# design.net
KiCad netlist of a schematic drawn in Altium Designer
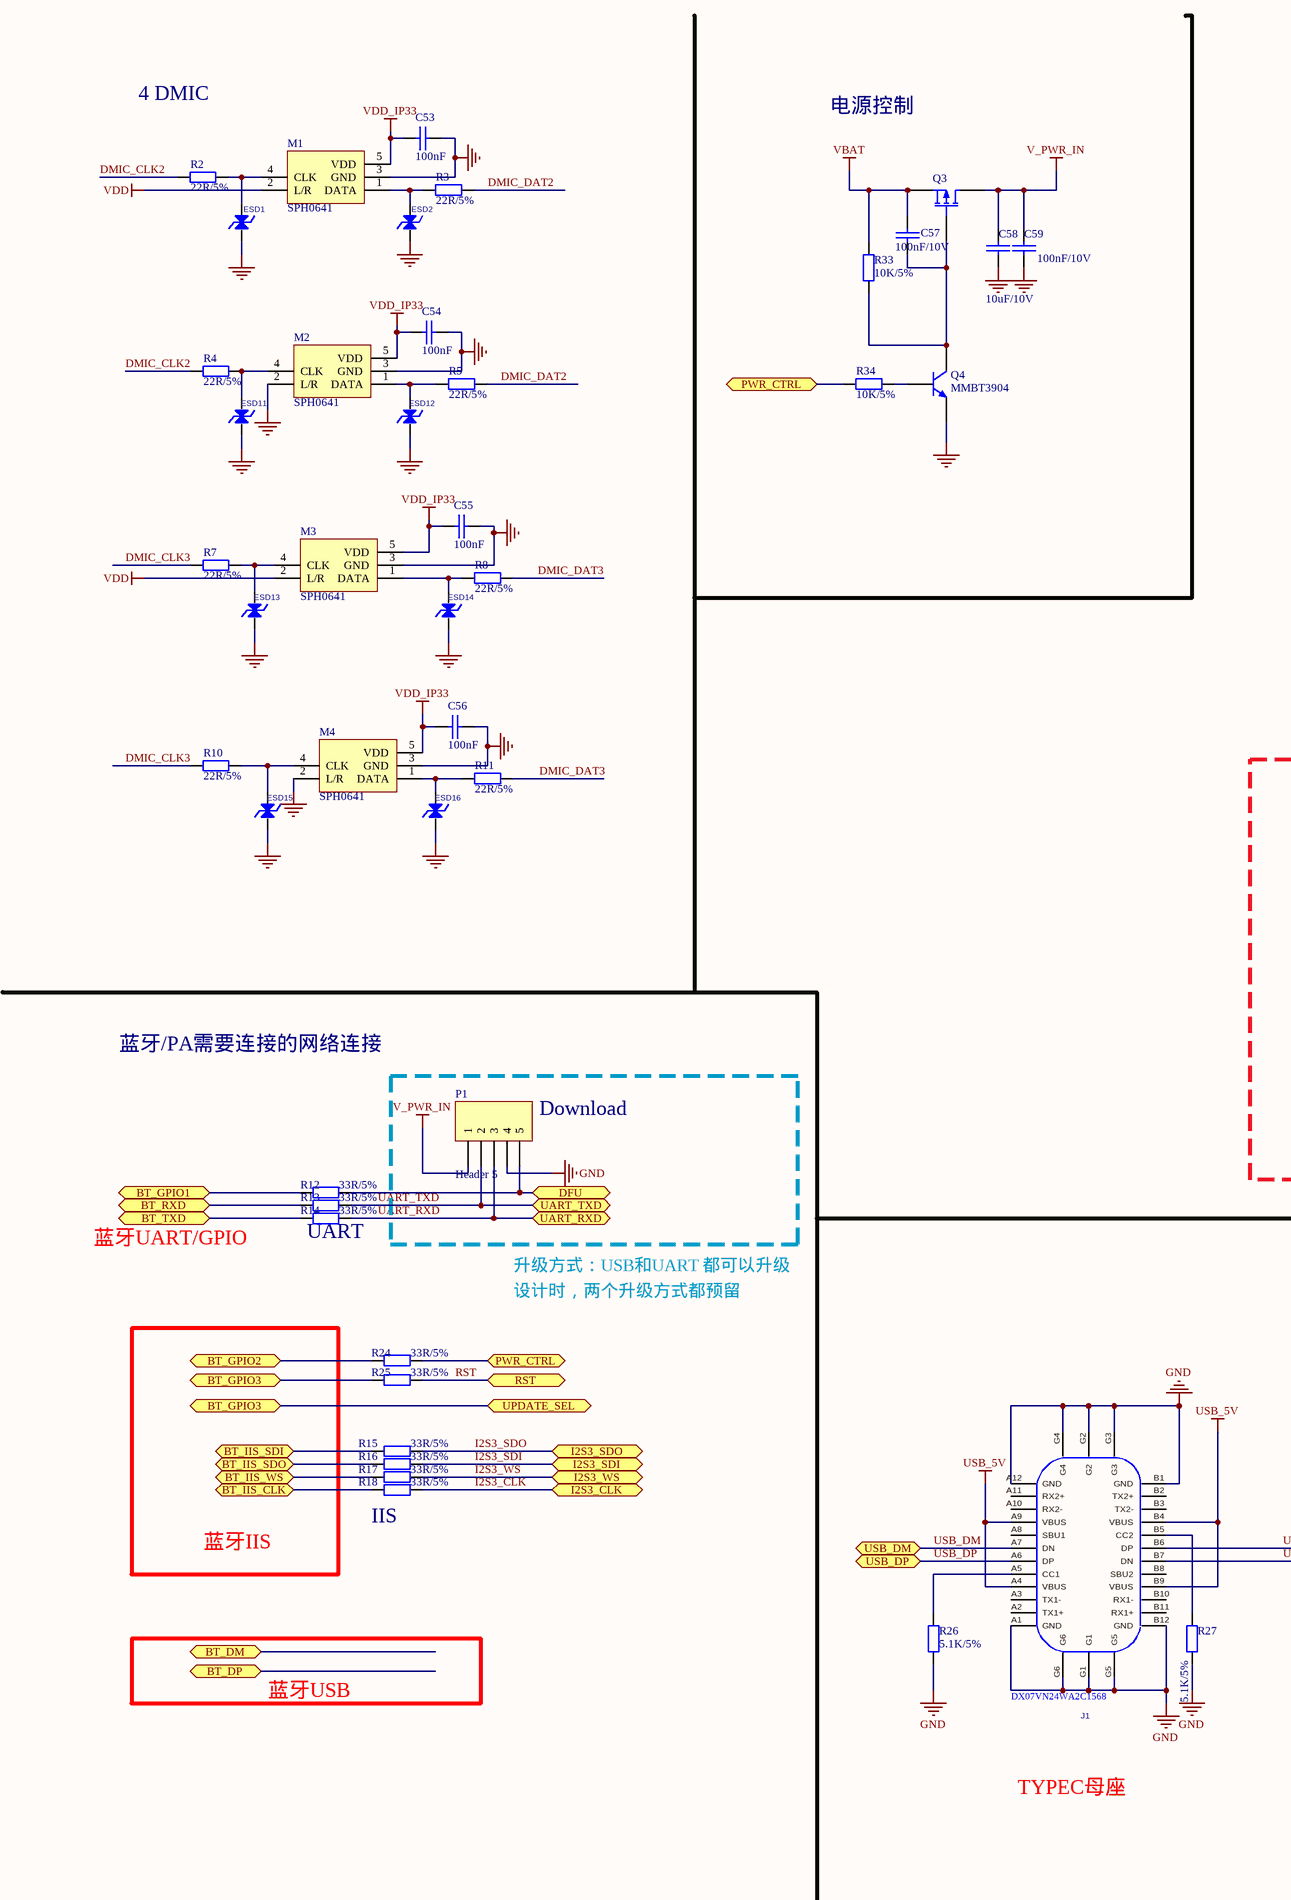
[diagram p0: 邮票孔参考设计.SchDoc, left]
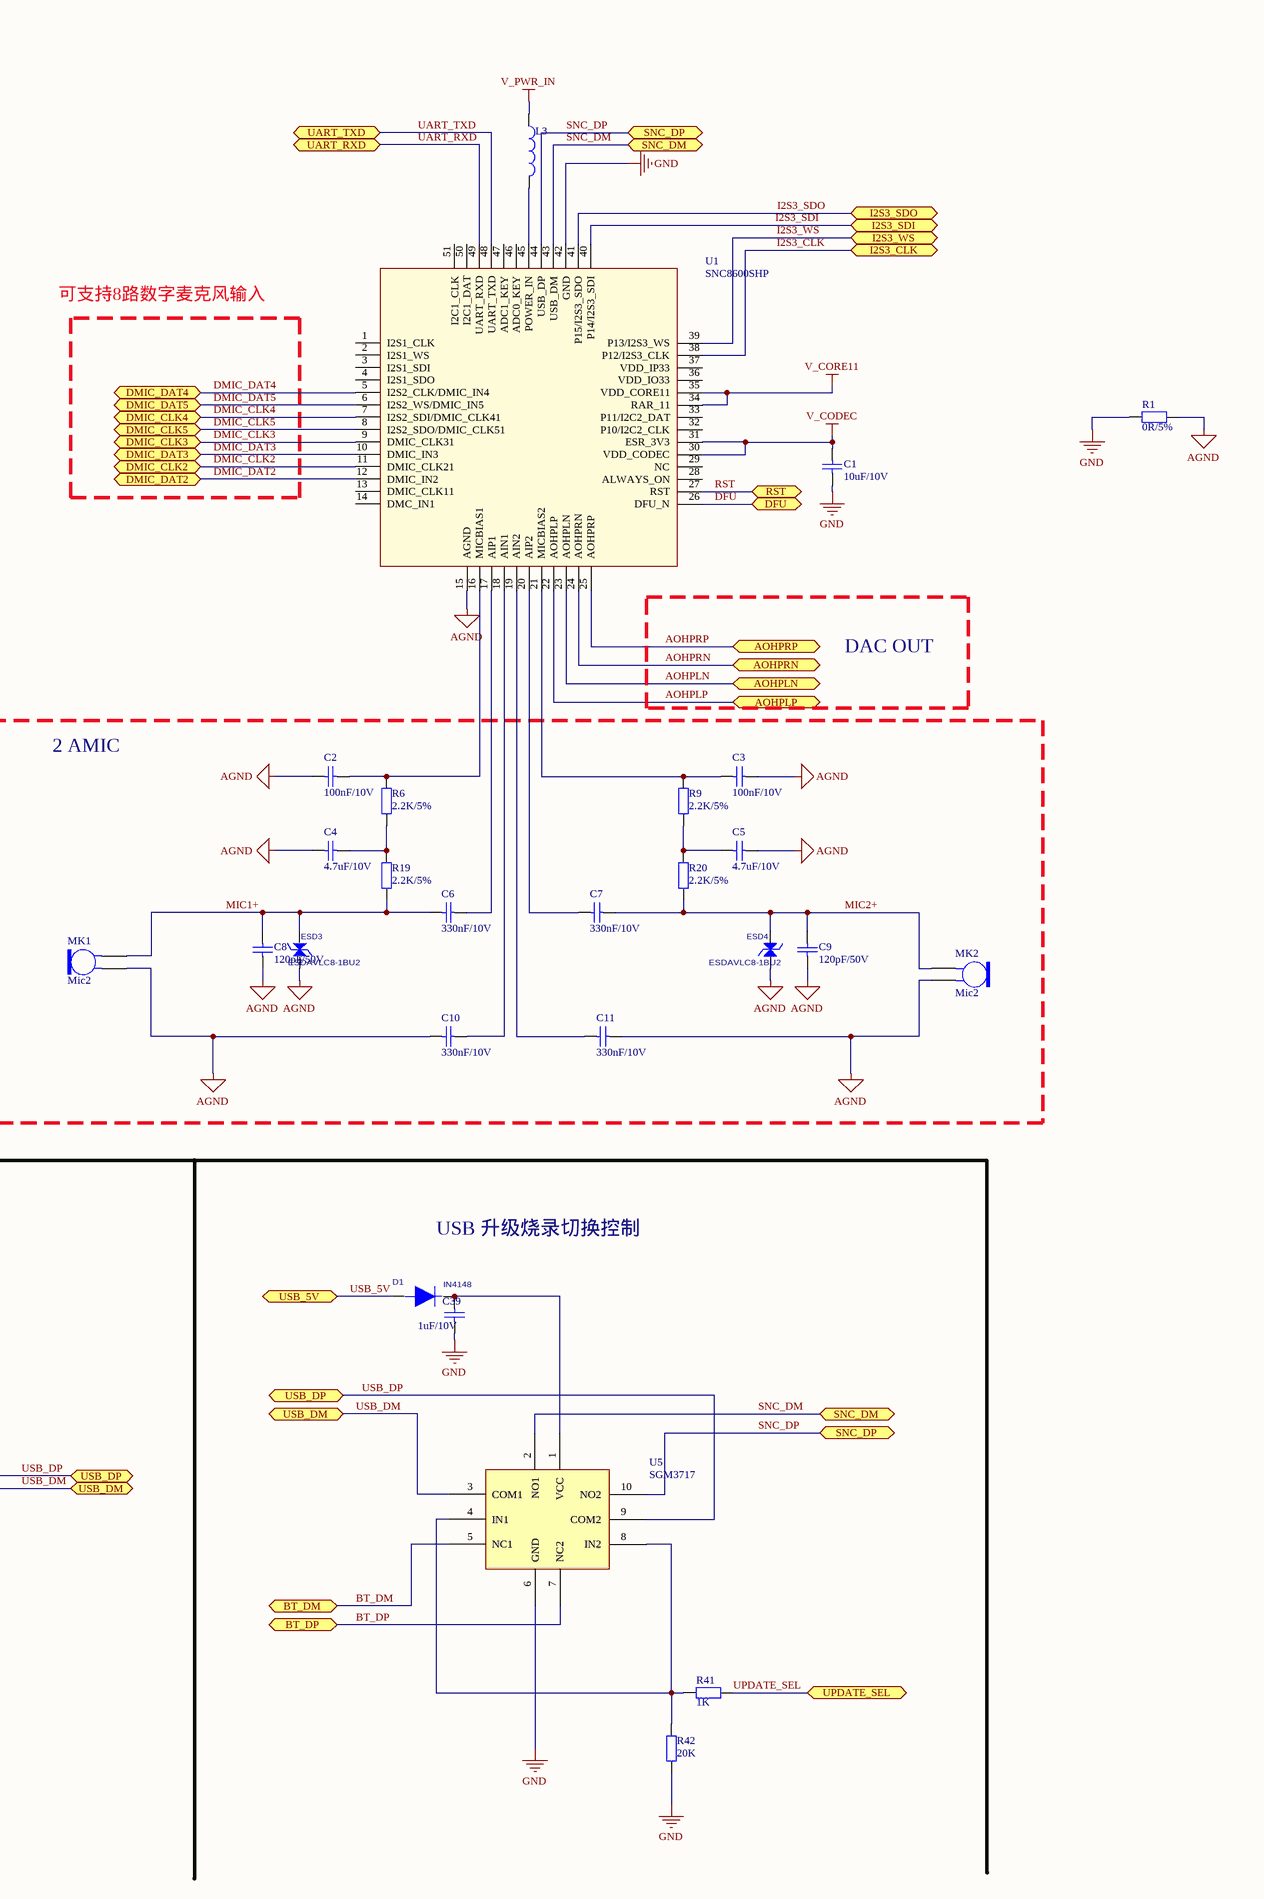
[diagram p1: 邮票孔参考设计.SchDoc, right]

(export (version "E")
  (design (tool "Eeschema 10.0.6"))
  (components
    (comp (ref "C1")
      (value "10uF/10V")
      (footprint "C0603")
      (description "Capacitor (Semiconductor SIM Model)")
      (fields (field (name "PUBLISHER") "Altium Limited"))
      (libsource (lib "Miscellaneous Devices") (part "Cap Semi"))
    )
    (comp (ref "C2")
      (value "100nF/10V")
      (footprint "C0402")
      (description "Capacitor (Semiconductor SIM Model)")
      (fields (field (name "PUBLISHER") "Altium Limited"))
      (libsource (lib "Miscellaneous Devices") (part "Cap Semi"))
    )
    (comp (ref "C3")
      (value "100nF/10V")
      (footprint "C0402")
      (description "Capacitor (Semiconductor SIM Model)")
      (fields (field (name "PUBLISHER") "Altium Limited"))
      (libsource (lib "Miscellaneous Devices") (part "Cap Semi"))
    )
    (comp (ref "C4")
      (value "4.7uF/10V")
      (footprint "0402")
      (description "Capacitor (Semiconductor SIM Model)")
      (fields (field (name "PUBLISHER") "Altium Limited"))
      (libsource (lib "Miscellaneous Devices") (part "Cap Semi"))
    )
    (comp (ref "C5")
      (value "4.7uF/10V")
      (footprint "0402")
      (description "Capacitor (Semiconductor SIM Model)")
      (fields (field (name "PUBLISHER") "Altium Limited"))
      (libsource (lib "Miscellaneous Devices") (part "Cap Semi"))
    )
    (comp (ref "C6")
      (value "330nF/10V")
      (footprint "C0402")
      (description "Capacitor (Semiconductor SIM Model)")
      (fields (field (name "PUBLISHER") "Altium Limited"))
      (libsource (lib "Miscellaneous Devices") (part "Cap Semi"))
    )
    (comp (ref "C7")
      (value "330nF/10V")
      (footprint "C0402")
      (description "Capacitor (Semiconductor SIM Model)")
      (fields (field (name "PUBLISHER") "Altium Limited"))
      (libsource (lib "Miscellaneous Devices") (part "Cap Semi"))
    )
    (comp (ref "C8")
      (value "120pF/50V")
      (footprint "C0402")
      (description "Capacitor (Semiconductor SIM Model)")
      (fields (field (name "PUBLISHER") "Altium Limited"))
      (libsource (lib "Miscellaneous Devices") (part "Cap Semi"))
    )
    (comp (ref "C9")
      (value "120pF/50V")
      (footprint "C0402")
      (description "Capacitor (Semiconductor SIM Model)")
      (fields (field (name "PUBLISHER") "Altium Limited"))
      (libsource (lib "Miscellaneous Devices") (part "Cap Semi"))
    )
    (comp (ref "C10")
      (value "330nF/10V")
      (footprint "C0402")
      (description "Capacitor (Semiconductor SIM Model)")
      (fields (field (name "PUBLISHER") "Altium Limited"))
      (libsource (lib "Miscellaneous Devices") (part "Cap Semi"))
    )
    (comp (ref "C11")
      (value "330nF/10V")
      (footprint "C0402")
      (description "Capacitor (Semiconductor SIM Model)")
      (fields (field (name "PUBLISHER") "Altium Limited"))
      (libsource (lib "Miscellaneous Devices") (part "Cap Semi"))
    )
    (comp (ref "C39")
      (value "1uF/10V")
      (footprint "C0603")
      (description "Capacitor (Semiconductor SIM Model)")
      (fields (field (name "PUBLISHER") "Altium Limited"))
      (libsource (lib "Miscellaneous Devices") (part "Cap Semi"))
    )
    (comp (ref "C53")
      (value "100nF")
      (footprint "0201")
      (description "Capacitor")
      (libsource (lib "MIC1") (part "CAP-0201"))
    )
    (comp (ref "C54")
      (value "100nF")
      (footprint "0201")
      (description "Capacitor")
      (libsource (lib "MIC1") (part "CAP-0201"))
    )
    (comp (ref "C55")
      (value "100nF")
      (footprint "0201")
      (description "Capacitor")
      (libsource (lib "MIC1") (part "CAP-0201"))
    )
    (comp (ref "C56")
      (value "100nF")
      (footprint "0201")
      (description "Capacitor")
      (libsource (lib "MIC1") (part "CAP-0201"))
    )
    (comp (ref "C57")
      (value "100nF/10V")
      (footprint "0201")
      (description "Capacitor")
      (libsource (lib "*") (part "CAP"))
    )
    (comp (ref "C58")
      (value "10uF/10V")
      (footprint "C0402")
      (description "Capacitor")
      (libsource (lib "电容") (part "普通电容"))
    )
    (comp (ref "C59")
      (value "100nF/10V")
      (footprint "0201")
      (description "Capacitor")
      (libsource (lib "电容") (part "普通电容"))
    )
    (comp (ref "D1")
      (value "IN4148")
      (footprint "SMD")
      (fields (field (name "Comment") "D-IN4148-SMT"))
      (libsource (lib "*") (part "D-IN4148-SMT"))
    )
    (comp (ref "ESD1")
      (value "~")
      (footprint "0402 DFN")
      (libsource (lib "EVB-SCH-LCD-202003152") (part "ESD"))
    )
    (comp (ref "ESD2")
      (value "~")
      (footprint "0402 DFN")
      (libsource (lib "EVB-SCH-LCD-202003152") (part "ESD"))
    )
    (comp (ref "ESD3")
      (value "ESDAVLC8-1BU2")
      (footprint "0402 DFN")
      (libsource (lib "EVB-SCH-LCD-202003152") (part "ESD"))
    )
    (comp (ref "ESD4")
      (value "ESDAVLC8-1BU2")
      (footprint "0402 DFN")
      (libsource (lib "EVB-SCH-LCD-202003152") (part "ESD"))
    )
    (comp (ref "ESD11")
      (value "~")
      (footprint "0402 DFN")
      (libsource (lib "EVB-SCH-LCD-202003152") (part "ESD"))
    )
    (comp (ref "ESD12")
      (value "~")
      (footprint "0402 DFN")
      (libsource (lib "EVB-SCH-LCD-202003152") (part "ESD"))
    )
    (comp (ref "ESD13")
      (value "~")
      (footprint "0402 DFN")
      (libsource (lib "EVB-SCH-LCD-202003152") (part "ESD"))
    )
    (comp (ref "ESD14")
      (value "~")
      (footprint "0402 DFN")
      (libsource (lib "EVB-SCH-LCD-202003152") (part "ESD"))
    )
    (comp (ref "ESD15")
      (value "~")
      (footprint "0402 DFN")
      (libsource (lib "EVB-SCH-LCD-202003152") (part "ESD"))
    )
    (comp (ref "ESD16")
      (value "~")
      (footprint "0402 DFN")
      (libsource (lib "EVB-SCH-LCD-202003152") (part "ESD"))
    )
    (comp (ref "J1")
      (value "TYPEC")
      (footprint "USB-TYPEC")
      (libsource (lib "EVB-SCH-LCD-202003152") (part "TYPEC"))
    )
    (comp (ref "L3")
      (value "~")
      (footprint "R0402")
      (description "Inductor")
      (fields (field (name "PUBLISHER") "Altium Limited"))
      (libsource (lib "Miscellaneous Devices") (part "Inductor"))
    )
    (comp (ref "M1")
      (value "SPH0641")
      (footprint "SPH_3526")
      (description "MEMS MICPHONE")
      (fields (field (name "PUBLISHER") "Altium Limited"))
      (libsource (lib "MIC1") (part "SPH0641"))
    )
    (comp (ref "M2")
      (value "SPH0641")
      (footprint "SPH_3526")
      (description "MEMS MICPHONE")
      (fields (field (name "PUBLISHER") "Altium Limited"))
      (libsource (lib "MIC1") (part "SPH0641"))
    )
    (comp (ref "M3")
      (value "SPH0641")
      (footprint "SPH_3526")
      (description "MEMS MICPHONE")
      (fields (field (name "PUBLISHER") "Altium Limited"))
      (libsource (lib "MIC1") (part "SPH0641"))
    )
    (comp (ref "M4")
      (value "SPH0641")
      (footprint "SPH_3526")
      (description "MEMS MICPHONE")
      (fields (field (name "PUBLISHER") "Altium Limited"))
      (libsource (lib "MIC1") (part "SPH0641"))
    )
    (comp (ref "MK1")
      (value "Mic2")
      (footprint "PIN2")
      (description "Microphone")
      (fields (field (name "PUBLISHER") "Altium Limited"))
      (libsource (lib "Miscellaneous Devices") (part "Mic2"))
    )
    (comp (ref "MK2")
      (value "Mic2")
      (footprint "PIN2")
      (description "Microphone")
      (fields (field (name "PUBLISHER") "Altium Limited"))
      (libsource (lib "Miscellaneous Devices") (part "Mic2"))
    )
    (comp (ref "P1")
      (value "Header 5")
      (footprint "HDR1X5")
      (description "Header, 5-Pin")
      (fields (field (name "PUBLISHER") "Altium Limited"))
      (libsource (lib "Miscellaneous Connectors") (part "Header 5"))
    )
    (comp (ref "Q3")
      (value "~")
      (footprint "SOT23_3407")
      (description "P-Channel MOSFET")
      (fields (field (name "PUBLISHER") "Altium Limited"))
      (libsource (lib "Miscellaneous Devices") (part "MOSFET-P"))
    )
    (comp (ref "Q4")
      (value "MMBT3904")
      (footprint "SOT23")
      (description "NPN General Purpose Amplifier")
      (fields (field (name "PUBLISHER") "Altium Limited"))
      (libsource (lib "Miscellaneous Devices") (part "2N3904"))
    )
    (comp (ref "R1")
      (value "0R/5%")
      (footprint "R0603")
      (description "Resistor")
      (fields (field (name "PUBLISHER") "Altium Limited"))
      (libsource (lib "") (part "Res2_2"))
    )
    (comp (ref "R2")
      (value "22R/5%")
      (footprint "0201")
      (description "Resistor")
      (fields (field (name "PUBLISHER") "Altium Limited"))
      (libsource (lib "Miscellaneous Devices") (part "Res2"))
    )
    (comp (ref "R3")
      (value "22R/5%")
      (footprint "0201")
      (description "Resistor")
      (fields (field (name "PUBLISHER") "Altium Limited"))
      (libsource (lib "Miscellaneous Devices") (part "Res2"))
    )
    (comp (ref "R4")
      (value "22R/5%")
      (footprint "0201")
      (description "Resistor")
      (fields (field (name "PUBLISHER") "Altium Limited"))
      (libsource (lib "Miscellaneous Devices") (part "Res2"))
    )
    (comp (ref "R5")
      (value "22R/5%")
      (footprint "0201")
      (description "Resistor")
      (fields (field (name "PUBLISHER") "Altium Limited"))
      (libsource (lib "Miscellaneous Devices") (part "Res2"))
    )
    (comp (ref "R6")
      (value "2.2K/5%")
      (footprint "R0402")
      (description "Resistor")
      (fields (field (name "PUBLISHER") "Altium Limited"))
      (libsource (lib "") (part "Res2_2"))
    )
    (comp (ref "R7")
      (value "22R/5%")
      (footprint "0201")
      (description "Resistor")
      (fields (field (name "PUBLISHER") "Altium Limited"))
      (libsource (lib "Miscellaneous Devices") (part "Res2"))
    )
    (comp (ref "R8")
      (value "22R/5%")
      (footprint "0201")
      (description "Resistor")
      (fields (field (name "PUBLISHER") "Altium Limited"))
      (libsource (lib "Miscellaneous Devices") (part "Res2"))
    )
    (comp (ref "R9")
      (value "2.2K/5%")
      (footprint "R0402")
      (description "Resistor")
      (fields (field (name "PUBLISHER") "Altium Limited"))
      (libsource (lib "") (part "Res2_1"))
    )
    (comp (ref "R10")
      (value "22R/5%")
      (footprint "0201")
      (description "Resistor")
      (fields (field (name "PUBLISHER") "Altium Limited"))
      (libsource (lib "Miscellaneous Devices") (part "Res2"))
    )
    (comp (ref "R11")
      (value "22R/5%")
      (footprint "0201")
      (description "Resistor")
      (fields (field (name "PUBLISHER") "Altium Limited"))
      (libsource (lib "Miscellaneous Devices") (part "Res2"))
    )
    (comp (ref "R12")
      (value "33R/5%")
      (footprint "R0603")
      (description "Resistor")
      (fields (field (name "PUBLISHER") "Altium Limited"))
      (libsource (lib "Miscellaneous Devices") (part "Res2"))
    )
    (comp (ref "R13")
      (value "33R/5%")
      (footprint "R0603")
      (description "Resistor")
      (fields (field (name "PUBLISHER") "Altium Limited"))
      (libsource (lib "Miscellaneous Devices") (part "Res2"))
    )
    (comp (ref "R14")
      (value "33R/5%")
      (footprint "R0603")
      (description "Resistor")
      (fields (field (name "PUBLISHER") "Altium Limited"))
      (libsource (lib "Miscellaneous Devices") (part "Res2"))
    )
    (comp (ref "R15")
      (value "33R/5%")
      (footprint "R0603")
      (description "Resistor")
      (fields (field (name "PUBLISHER") "Altium Limited"))
      (libsource (lib "Miscellaneous Devices") (part "Res2"))
    )
    (comp (ref "R16")
      (value "33R/5%")
      (footprint "R0603")
      (description "Resistor")
      (fields (field (name "PUBLISHER") "Altium Limited"))
      (libsource (lib "Miscellaneous Devices") (part "Res2"))
    )
    (comp (ref "R17")
      (value "33R/5%")
      (footprint "R0603")
      (description "Resistor")
      (fields (field (name "PUBLISHER") "Altium Limited"))
      (libsource (lib "Miscellaneous Devices") (part "Res2"))
    )
    (comp (ref "R18")
      (value "33R/5%")
      (footprint "R0603")
      (description "Resistor")
      (fields (field (name "PUBLISHER") "Altium Limited"))
      (libsource (lib "Miscellaneous Devices") (part "Res2"))
    )
    (comp (ref "R19")
      (value "2.2K/5%")
      (footprint "R0402")
      (description "Resistor")
      (fields (field (name "PUBLISHER") "Altium Limited"))
      (libsource (lib "") (part "Res2_2"))
    )
    (comp (ref "R20")
      (value "2.2K/5%")
      (footprint "R0402")
      (description "Resistor")
      (fields (field (name "PUBLISHER") "Altium Limited"))
      (libsource (lib "") (part "Res2_1"))
    )
    (comp (ref "R24")
      (value "33R/5%")
      (footprint "R0603")
      (description "Resistor")
      (fields (field (name "PUBLISHER") "Altium Limited"))
      (libsource (lib "Miscellaneous Devices") (part "Res2"))
    )
    (comp (ref "R25")
      (value "33R/5%")
      (footprint "R0603")
      (description "Resistor")
      (fields (field (name "PUBLISHER") "Altium Limited"))
      (libsource (lib "Miscellaneous Devices") (part "Res2"))
    )
    (comp (ref "R26")
      (value "5.1K/5%")
      (footprint "R0603")
      (description "Resistor")
      (fields (field (name "PUBLISHER") "Altium Limited"))
      (libsource (lib "") (part "Res2_1"))
    )
    (comp (ref "R27")
      (value "5.1K/5%")
      (footprint "R0603")
      (description "Resistor")
      (fields (field (name "PUBLISHER") "Altium Limited"))
      (libsource (lib "") (part "Res2_1"))
    )
    (comp (ref "R33")
      (value "10K/5%")
      (footprint "0201")
      (description "Resistor")
      (fields (field (name "PUBLISHER") "Altium Limited"))
      (libsource (lib "") (part "Res2_1"))
    )
    (comp (ref "R34")
      (value "10K/5%")
      (footprint "0201")
      (description "Resistor")
      (fields (field (name "PUBLISHER") "Altium Limited"))
      (libsource (lib "Miscellaneous Devices") (part "Res2"))
    )
    (comp (ref "R41")
      (value "1K")
      (footprint "R0603")
      (description "Resistor")
      (fields (field (name "PUBLISHER") "Altium Limited"))
      (libsource (lib "") (part "Res2_2"))
    )
    (comp (ref "R42")
      (value "20K")
      (footprint "R0603")
      (description "Resistor")
      (fields (field (name "PUBLISHER") "Altium Limited"))
      (libsource (lib "") (part "Res2_1"))
    )
    (comp (ref "U1") (value "SNC8600SHP") (libsource (lib "EVB-SCH-LCD-202003152") (part "SNC8600SHP")))
    (comp (ref "U5")
      (value "SGM3717")
      (footprint "UQFN10")
      (libsource (lib "EVB-SCH-LCD-202003152") (part "NLAS2750"))
    )
  )
  (nets
    (net (code "1") (name "/AOHPLN") (class "Default")
      (node (ref "U1") (pin "23") (pinfunction "AOHPLN_23") (pintype "passive"))
    )
    (net (code "2") (name "/AOHPLP") (class "Default")
      (node (ref "U1") (pin "22") (pinfunction "AOHPLP_22") (pintype "passive"))
    )
    (net (code "3") (name "/AOHPRN") (class "Default")
      (node (ref "U1") (pin "24") (pinfunction "AOHPRN_24") (pintype "passive"))
    )
    (net (code "4") (name "/AOHPRP") (class "Default")
      (node (ref "U1") (pin "25") (pinfunction "AOHPRP_25") (pintype "passive"))
    )
    (net (code "5") (name "/BT_DM") (class "Default")
      (node (ref "U5") (pin "5") (pinfunction "NC1_5") (pintype "passive"))
    )
    (net (code "6") (name "/BT_DP") (class "Default")
      (node (ref "U5") (pin "7") (pinfunction "NC2_7") (pintype "passive"))
    )
    (net (code "7") (name "/BT_GPIO1") (class "Default")
      (node (ref "R12") (pin "1") (pinfunction "1_1") (pintype "passive"))
    )
    (net (code "8") (name "/BT_GPIO2") (class "Default")
      (node (ref "R24") (pin "1") (pinfunction "1_1") (pintype "passive"))
    )
    (net (code "9") (name "/BT_IIS_CLK") (class "Default")
      (node (ref "R18") (pin "1") (pinfunction "1_1") (pintype "passive"))
    )
    (net (code "10") (name "/BT_IIS_SDI") (class "Default")
      (node (ref "R15") (pin "1") (pinfunction "1_1") (pintype "passive"))
    )
    (net (code "11") (name "/BT_IIS_SDO") (class "Default")
      (node (ref "R16") (pin "1") (pinfunction "1_1") (pintype "passive"))
    )
    (net (code "12") (name "/BT_IIS_WS") (class "Default")
      (node (ref "R17") (pin "1") (pinfunction "1_1") (pintype "passive"))
    )
    (net (code "13") (name "/BT_RXD") (class "Default")
      (node (ref "R13") (pin "1") (pinfunction "1_1") (pintype "passive"))
    )
    (net (code "14") (name "/BT_TXD") (class "Default")
      (node (ref "R14") (pin "1") (pinfunction "1_1") (pintype "passive"))
    )
    (net (code "15") (name "/DFU") (class "Default")
      (node (ref "P1") (pin "5") (pinfunction "5_5") (pintype "passive"))
      (node (ref "R12") (pin "2") (pinfunction "2_2") (pintype "passive"))
      (node (ref "U1") (pin "26") (pinfunction "DFU_N_26") (pintype "passive"))
    )
    (net (code "16") (name "/DMIC_CLK2") (class "Default")
      (node (ref "R2") (pin "1") (pinfunction "1_1") (pintype "passive"))
      (node (ref "R4") (pin "1") (pinfunction "1_1") (pintype "passive"))
      (node (ref "U1") (pin "11") (pinfunction "DMIC_CLK21_11") (pintype "passive"))
    )
    (net (code "17") (name "/DMIC_CLK3") (class "Default")
      (node (ref "R10") (pin "1") (pinfunction "1_1") (pintype "passive"))
      (node (ref "R7") (pin "1") (pinfunction "1_1") (pintype "passive"))
      (node (ref "U1") (pin "9") (pinfunction "DMIC_CLK31_9") (pintype "passive"))
    )
    (net (code "18") (name "/DMIC_CLK4") (class "Default")
      (node (ref "U1") (pin "7") (pinfunction "I2S2_SDI/DMIC_CLK41_7") (pintype "passive"))
    )
    (net (code "19") (name "/DMIC_CLK5") (class "Default")
      (node (ref "U1") (pin "8") (pinfunction "I2S2_SDO/DMIC_CLK51_8") (pintype "passive"))
    )
    (net (code "20") (name "/DMIC_DAT2") (class "Default")
      (node (ref "R3") (pin "2") (pinfunction "2_2") (pintype "passive"))
      (node (ref "R5") (pin "2") (pinfunction "2_2") (pintype "passive"))
      (node (ref "U1") (pin "12") (pinfunction "DMIC_IN2_12") (pintype "passive"))
    )
    (net (code "21") (name "/DMIC_DAT3") (class "Default")
      (node (ref "R11") (pin "2") (pinfunction "2_2") (pintype "passive"))
      (node (ref "R8") (pin "2") (pinfunction "2_2") (pintype "passive"))
      (node (ref "U1") (pin "10") (pinfunction "DMIC_IN3_10") (pintype "passive"))
    )
    (net (code "22") (name "/DMIC_DAT4") (class "Default")
      (node (ref "U1") (pin "5") (pinfunction "I2S2_CLK/DMIC_IN4_5") (pintype "passive"))
    )
    (net (code "23") (name "/DMIC_DAT5") (class "Default")
      (node (ref "U1") (pin "6") (pinfunction "I2S2_WS/DMIC_IN5_6") (pintype "passive"))
    )
    (net (code "24") (name "/I2S3_CLK") (class "Default")
      (node (ref "R18") (pin "2") (pinfunction "2_2") (pintype "passive"))
      (node (ref "U1") (pin "38") (pinfunction "P12/I2S3_CLK_38") (pintype "passive"))
    )
    (net (code "25") (name "/I2S3_SDI") (class "Default")
      (node (ref "R16") (pin "2") (pinfunction "2_2") (pintype "passive"))
      (node (ref "U1") (pin "40") (pinfunction "P14/I2S3_SDI_40") (pintype "passive"))
    )
    (net (code "26") (name "/I2S3_SDO") (class "Default")
      (node (ref "R15") (pin "2") (pinfunction "2_2") (pintype "passive"))
      (node (ref "U1") (pin "41") (pinfunction "P15/I2S3_SDO_41") (pintype "passive"))
    )
    (net (code "27") (name "/I2S3_WS") (class "Default")
      (node (ref "R17") (pin "2") (pinfunction "2_2") (pintype "passive"))
      (node (ref "U1") (pin "39") (pinfunction "P13/I2S3_WS_39") (pintype "passive"))
    )
    (net (code "28") (name "/MIC1+") (class "Default")
      (node (ref "C6") (pin "1") (pinfunction "1_1") (pintype "passive"))
      (node (ref "C8") (pin "1") (pinfunction "1_1") (pintype "passive"))
      (node (ref "ESD3") (pin "1") (pinfunction "1_1") (pintype "passive"))
      (node (ref "MK1") (pin "2") (pinfunction "2_2") (pintype "passive"))
      (node (ref "R19") (pin "2") (pinfunction "2_2") (pintype "passive"))
    )
    (net (code "29") (name "/MIC2+") (class "Default")
      (node (ref "C7") (pin "1") (pinfunction "1_1") (pintype "passive"))
      (node (ref "C9") (pin "1") (pinfunction "1_1") (pintype "passive"))
      (node (ref "ESD4") (pin "1") (pinfunction "1_1") (pintype "passive"))
      (node (ref "MK2") (pin "1") (pinfunction "1_1") (pintype "passive"))
      (node (ref "R20") (pin "2") (pinfunction "2_2") (pintype "passive"))
    )
    (net (code "30") (name "/PWR_CTRL") (class "Default")
      (node (ref "R24") (pin "2") (pinfunction "2_2") (pintype "passive"))
      (node (ref "R34") (pin "1") (pinfunction "1_1") (pintype "passive"))
    )
    (net (code "31") (name "/RST") (class "Default")
      (node (ref "R25") (pin "2") (pinfunction "2_2") (pintype "passive"))
      (node (ref "U1") (pin "27") (pinfunction "RST_27") (pintype "passive"))
    )
    (net (code "32") (name "/SNC_DM") (class "Default")
      (node (ref "U1") (pin "43") (pinfunction "USB_DM_43") (pintype "passive"))
      (node (ref "U5") (pin "2") (pinfunction "NO1_2") (pintype "passive"))
    )
    (net (code "33") (name "/SNC_DP") (class "Default")
      (node (ref "U1") (pin "44") (pinfunction "USB_DP_44") (pintype "passive"))
      (node (ref "U5") (pin "10") (pinfunction "NO2_10") (pintype "passive"))
    )
    (net (code "34") (name "/UART_RXD") (class "Default")
      (node (ref "P1") (pin "3") (pinfunction "3_3") (pintype "passive"))
      (node (ref "R14") (pin "2") (pinfunction "2_2") (pintype "passive"))
      (node (ref "U1") (pin "49") (pinfunction "UART_RXD_49") (pintype "passive"))
    )
    (net (code "35") (name "/UART_TXD") (class "Default")
      (node (ref "P1") (pin "2") (pinfunction "2_2") (pintype "passive"))
      (node (ref "R13") (pin "2") (pinfunction "2_2") (pintype "passive"))
      (node (ref "U1") (pin "48") (pinfunction "UART_TXD_48") (pintype "passive"))
    )
    (net (code "36") (name "/UPDATE_SEL") (class "Default")
      (node (ref "R25") (pin "1") (pinfunction "1_1") (pintype "passive"))
      (node (ref "R41") (pin "1") (pinfunction "1_1") (pintype "passive"))
    )
    (net (code "37") (name "/USB_DM") (class "Default")
      (node (ref "J1") (pin "A7") (pinfunction "DN_A7") (pintype "passive"))
      (node (ref "J1") (pin "B7") (pinfunction "DN_B7") (pintype "passive"))
      (node (ref "U5") (pin "3") (pinfunction "COM1_3") (pintype "passive"))
    )
    (net (code "38") (name "/USB_DP") (class "Default")
      (node (ref "J1") (pin "A6") (pinfunction "DP_A6") (pintype "passive"))
      (node (ref "J1") (pin "B6") (pinfunction "DP_B6") (pintype "passive"))
      (node (ref "U5") (pin "9") (pinfunction "COM2_9") (pintype "passive"))
    )
    (net (code "39") (name "AGND") (class "Default")
      (node (ref "C10") (pin "1") (pinfunction "1_1") (pintype "passive"))
      (node (ref "C11") (pin "1") (pinfunction "1_1") (pintype "passive"))
      (node (ref "C2") (pin "2") (pinfunction "2_2") (pintype "passive"))
      (node (ref "C3") (pin "2") (pinfunction "2_2") (pintype "passive"))
      (node (ref "C4") (pin "2") (pinfunction "2_2") (pintype "passive"))
      (node (ref "C5") (pin "2") (pinfunction "2_2") (pintype "passive"))
      (node (ref "C8") (pin "2") (pinfunction "2_2") (pintype "passive"))
      (node (ref "C9") (pin "2") (pinfunction "2_2") (pintype "passive"))
      (node (ref "ESD3") (pin "2") (pinfunction "2_2") (pintype "passive"))
      (node (ref "ESD4") (pin "2") (pinfunction "2_2") (pintype "passive"))
      (node (ref "MK1") (pin "1") (pinfunction "1_1") (pintype "passive"))
      (node (ref "MK2") (pin "2") (pinfunction "2_2") (pintype "passive"))
      (node (ref "R1") (pin "1") (pinfunction "1_1") (pintype "passive"))
      (node (ref "U1") (pin "15") (pinfunction "AGND_15") (pintype "passive"))
    )
    (net (code "40") (name "GND") (class "Default")
      (node (ref "C1") (pin "1") (pinfunction "1_1") (pintype "passive"))
      (node (ref "C39") (pin "1") (pinfunction "1_1") (pintype "passive"))
      (node (ref "C53") (pin "1") (pinfunction "1_1") (pintype "passive"))
      (node (ref "C54") (pin "1") (pinfunction "1_1") (pintype "passive"))
      (node (ref "C55") (pin "1") (pinfunction "1_1") (pintype "passive"))
      (node (ref "C56") (pin "1") (pinfunction "1_1") (pintype "passive"))
      (node (ref "C58") (pin "1") (pinfunction "1_1") (pintype "passive"))
      (node (ref "C59") (pin "1") (pinfunction "1_1") (pintype "passive"))
      (node (ref "ESD1") (pin "2") (pinfunction "2_2") (pintype "passive"))
      (node (ref "ESD11") (pin "2") (pinfunction "2_2") (pintype "passive"))
      (node (ref "ESD12") (pin "2") (pinfunction "2_2") (pintype "passive"))
      (node (ref "ESD13") (pin "2") (pinfunction "2_2") (pintype "passive"))
      (node (ref "ESD14") (pin "2") (pinfunction "2_2") (pintype "passive"))
      (node (ref "ESD15") (pin "2") (pinfunction "2_2") (pintype "passive"))
      (node (ref "ESD16") (pin "2") (pinfunction "2_2") (pintype "passive"))
      (node (ref "ESD2") (pin "2") (pinfunction "2_2") (pintype "passive"))
      (node (ref "J1") (pin "A1") (pinfunction "GND_A1") (pintype "passive"))
      (node (ref "J1") (pin "A12") (pinfunction "GND_A12") (pintype "passive"))
      (node (ref "J1") (pin "B1") (pinfunction "GND_B1") (pintype "passive"))
      (node (ref "J1") (pin "B12") (pinfunction "GND_B12") (pintype "passive"))
      (node (ref "J1") (pin "G1") (pinfunction "G1_G1") (pintype "passive"))
      (node (ref "J1") (pin "G2") (pinfunction "G2_G2") (pintype "passive"))
      (node (ref "J1") (pin "G3") (pinfunction "G3_G3") (pintype "passive"))
      (node (ref "J1") (pin "G4") (pinfunction "G4_G4") (pintype "passive"))
      (node (ref "J1") (pin "G5") (pinfunction "G5_G5") (pintype "passive"))
      (node (ref "J1") (pin "G6") (pinfunction "G6_G6") (pintype "passive"))
      (node (ref "M1") (pin "3") (pinfunction "GND_3") (pintype "power_in"))
      (node (ref "M2") (pin "2") (pinfunction "L/R_2") (pintype "passive"))
      (node (ref "M2") (pin "3") (pinfunction "GND_3") (pintype "power_in"))
      (node (ref "M3") (pin "3") (pinfunction "GND_3") (pintype "power_in"))
      (node (ref "M4") (pin "2") (pinfunction "L/R_2") (pintype "passive"))
      (node (ref "M4") (pin "3") (pinfunction "GND_3") (pintype "power_in"))
      (node (ref "P1") (pin "4") (pinfunction "4_4") (pintype "passive"))
      (node (ref "Q4") (pin "2") (pinfunction "E_2") (pintype "passive"))
      (node (ref "R1") (pin "2") (pinfunction "2_2") (pintype "passive"))
      (node (ref "R26") (pin "2") (pinfunction "2_2") (pintype "passive"))
      (node (ref "R27") (pin "2") (pinfunction "2_2") (pintype "passive"))
      (node (ref "R42") (pin "2") (pinfunction "2_2") (pintype "passive"))
      (node (ref "U1") (pin "42") (pinfunction "GND_42") (pintype "passive"))
      (node (ref "U5") (pin "6") (pinfunction "GND_6") (pintype "passive"))
    )
    (net (code "41") (name "Net-(C4-Pad1)") (class "Default")
      (node (ref "C4") (pin "1") (pinfunction "1_1") (pintype "passive"))
      (node (ref "R19") (pin "1") (pinfunction "1_1") (pintype "passive"))
      (node (ref "R6") (pin "2") (pinfunction "2_2") (pintype "passive"))
    )
    (net (code "42") (name "Net-(C5-Pad1)") (class "Default")
      (node (ref "C5") (pin "1") (pinfunction "1_1") (pintype "passive"))
      (node (ref "R20") (pin "1") (pinfunction "1_1") (pintype "passive"))
      (node (ref "R9") (pin "2") (pinfunction "2_2") (pintype "passive"))
    )
    (net (code "43") (name "Net-(J1-CC1)") (class "Default")
      (node (ref "J1") (pin "A5") (pinfunction "CC1_A5") (pintype "passive"))
      (node (ref "R26") (pin "1") (pinfunction "1_1") (pintype "passive"))
    )
    (net (code "44") (name "Net-(J1-CC2)") (class "Default")
      (node (ref "J1") (pin "B5") (pinfunction "CC2_B5") (pintype "passive"))
      (node (ref "R27") (pin "1") (pinfunction "1_1") (pintype "passive"))
    )
    (net (code "45") (name "Net-(M1-CLK)") (class "Default")
      (node (ref "ESD1") (pin "1") (pinfunction "1_1") (pintype "passive"))
      (node (ref "M1") (pin "4") (pinfunction "CLK_4") (pintype "power_in"))
      (node (ref "R2") (pin "2") (pinfunction "2_2") (pintype "passive"))
    )
    (net (code "46") (name "Net-(M1-DATA)") (class "Default")
      (node (ref "ESD2") (pin "1") (pinfunction "1_1") (pintype "passive"))
      (node (ref "M1") (pin "1") (pinfunction "DATA_1") (pintype "passive"))
      (node (ref "R3") (pin "1") (pinfunction "1_1") (pintype "passive"))
    )
    (net (code "47") (name "Net-(M2-CLK)") (class "Default")
      (node (ref "ESD11") (pin "1") (pinfunction "1_1") (pintype "passive"))
      (node (ref "M2") (pin "4") (pinfunction "CLK_4") (pintype "power_in"))
      (node (ref "R4") (pin "2") (pinfunction "2_2") (pintype "passive"))
    )
    (net (code "48") (name "Net-(M2-DATA)") (class "Default")
      (node (ref "ESD12") (pin "1") (pinfunction "1_1") (pintype "passive"))
      (node (ref "M2") (pin "1") (pinfunction "DATA_1") (pintype "passive"))
      (node (ref "R5") (pin "1") (pinfunction "1_1") (pintype "passive"))
    )
    (net (code "49") (name "Net-(M3-CLK)") (class "Default")
      (node (ref "ESD13") (pin "1") (pinfunction "1_1") (pintype "passive"))
      (node (ref "M3") (pin "4") (pinfunction "CLK_4") (pintype "power_in"))
      (node (ref "R7") (pin "2") (pinfunction "2_2") (pintype "passive"))
    )
    (net (code "50") (name "Net-(M3-DATA)") (class "Default")
      (node (ref "ESD14") (pin "1") (pinfunction "1_1") (pintype "passive"))
      (node (ref "M3") (pin "1") (pinfunction "DATA_1") (pintype "passive"))
      (node (ref "R8") (pin "1") (pinfunction "1_1") (pintype "passive"))
    )
    (net (code "51") (name "Net-(M4-CLK)") (class "Default")
      (node (ref "ESD15") (pin "1") (pinfunction "1_1") (pintype "passive"))
      (node (ref "M4") (pin "4") (pinfunction "CLK_4") (pintype "power_in"))
      (node (ref "R10") (pin "2") (pinfunction "2_2") (pintype "passive"))
    )
    (net (code "52") (name "Net-(M4-DATA)") (class "Default")
      (node (ref "ESD16") (pin "1") (pinfunction "1_1") (pintype "passive"))
      (node (ref "M4") (pin "1") (pinfunction "DATA_1") (pintype "passive"))
      (node (ref "R11") (pin "1") (pinfunction "1_1") (pintype "passive"))
    )
    (net (code "53") (name "Net-(Q3-G)") (class "Default")
      (node (ref "C57") (pin "1") (pinfunction "1_1") (pintype "passive"))
      (node (ref "Q3") (pin "2") (pinfunction "G_2") (pintype "passive"))
      (node (ref "Q4") (pin "3") (pinfunction "C_3") (pintype "passive"))
      (node (ref "R33") (pin "2") (pinfunction "2_2") (pintype "passive"))
    )
    (net (code "54") (name "Net-(Q4-B)") (class "Default")
      (node (ref "Q4") (pin "1") (pinfunction "B_1") (pintype "passive"))
      (node (ref "R34") (pin "2") (pinfunction "2_2") (pintype "passive"))
    )
    (net (code "55") (name "Net-(U1-AIN1)") (class "Default")
      (node (ref "C10") (pin "2") (pinfunction "2_2") (pintype "passive"))
      (node (ref "U1") (pin "18") (pinfunction "AIN1_18") (pintype "passive"))
    )
    (net (code "56") (name "Net-(U1-AIN2)") (class "Default")
      (node (ref "C11") (pin "2") (pinfunction "2_2") (pintype "passive"))
      (node (ref "U1") (pin "19") (pinfunction "AIN2_19") (pintype "passive"))
    )
    (net (code "57") (name "Net-(U1-AIP1)") (class "Default")
      (node (ref "C6") (pin "2") (pinfunction "2_2") (pintype "passive"))
      (node (ref "U1") (pin "17") (pinfunction "AIP1_17") (pintype "passive"))
    )
    (net (code "58") (name "Net-(U1-AIP2)") (class "Default")
      (node (ref "C7") (pin "2") (pinfunction "2_2") (pintype "passive"))
      (node (ref "U1") (pin "20") (pinfunction "AIP2_20") (pintype "passive"))
    )
    (net (code "59") (name "Net-(U1-MICBIAS1)") (class "Default")
      (node (ref "C2") (pin "1") (pinfunction "1_1") (pintype "passive"))
      (node (ref "R6") (pin "1") (pinfunction "1_1") (pintype "passive"))
      (node (ref "U1") (pin "16") (pinfunction "MICBIAS1_16") (pintype "passive"))
    )
    (net (code "60") (name "Net-(U1-MICBIAS2)") (class "Default")
      (node (ref "C3") (pin "1") (pinfunction "1_1") (pintype "passive"))
      (node (ref "R9") (pin "1") (pinfunction "1_1") (pintype "passive"))
      (node (ref "U1") (pin "21") (pinfunction "MICBIAS2_21") (pintype "passive"))
    )
    (net (code "61") (name "Net-(U1-POWER_IN)") (class "Default")
      (node (ref "L3") (pin "2") (pinfunction "2_2") (pintype "passive"))
      (node (ref "U1") (pin "45") (pinfunction "POWER_IN_45") (pintype "passive"))
    )
    (net (code "62") (name "Net-(U5-IN1)") (class "Default")
      (node (ref "R41") (pin "2") (pinfunction "2_2") (pintype "passive"))
      (node (ref "R42") (pin "1") (pinfunction "1_1") (pintype "passive"))
      (node (ref "U5") (pin "4") (pinfunction "IN1_4") (pintype "passive"))
      (node (ref "U5") (pin "8") (pinfunction "IN2_8") (pintype "passive"))
    )
    (net (code "63") (name "Net-(U5-VCC)") (class "Default")
      (node (ref "C39") (pin "2") (pinfunction "2_2") (pintype "passive"))
      (node (ref "D1") (pin "2") (pinfunction "2_2") (pintype "passive"))
      (node (ref "U5") (pin "1") (pinfunction "VCC_1") (pintype "passive"))
    )
    (net (code "64") (name "USB_5V") (class "Default")
      (node (ref "D1") (pin "1") (pinfunction "1_1") (pintype "passive"))
      (node (ref "J1") (pin "A4") (pinfunction "VBUS_A4") (pintype "passive"))
      (node (ref "J1") (pin "A9") (pinfunction "VBUS_A9") (pintype "passive"))
      (node (ref "J1") (pin "B4") (pinfunction "VBUS_B4") (pintype "passive"))
      (node (ref "J1") (pin "B9") (pinfunction "VBUS_B9") (pintype "passive"))
    )
    (net (code "65") (name "VBAT") (class "Default")
      (node (ref "C57") (pin "2") (pinfunction "2_2") (pintype "passive"))
      (node (ref "Q3") (pin "3") (pinfunction "S_3") (pintype "passive"))
      (node (ref "R33") (pin "1") (pinfunction "1_1") (pintype "passive"))
    )
    (net (code "66") (name "VDD") (class "Default")
      (node (ref "M1") (pin "2") (pinfunction "L/R_2") (pintype "passive"))
      (node (ref "M3") (pin "2") (pinfunction "L/R_2") (pintype "passive"))
    )
    (net (code "67") (name "VDD_IP33") (class "Default")
      (node (ref "C53") (pin "2") (pinfunction "2_2") (pintype "passive"))
      (node (ref "C54") (pin "2") (pinfunction "2_2") (pintype "passive"))
      (node (ref "C55") (pin "2") (pinfunction "2_2") (pintype "passive"))
      (node (ref "C56") (pin "2") (pinfunction "2_2") (pintype "passive"))
      (node (ref "M1") (pin "5") (pinfunction "VDD_5") (pintype "power_in"))
      (node (ref "M2") (pin "5") (pinfunction "VDD_5") (pintype "power_in"))
      (node (ref "M3") (pin "5") (pinfunction "VDD_5") (pintype "power_in"))
      (node (ref "M4") (pin "5") (pinfunction "VDD_5") (pintype "power_in"))
    )
    (net (code "68") (name "V_CODEC") (class "Default")
      (node (ref "C1") (pin "2") (pinfunction "2_2") (pintype "passive"))
      (node (ref "U1") (pin "30") (pinfunction "VDD_CODEC_30") (pintype "passive"))
      (node (ref "U1") (pin "31") (pinfunction "ESR_3V3_31") (pintype "passive"))
    )
    (net (code "69") (name "V_CORE11") (class "Default")
      (node (ref "U1") (pin "34") (pinfunction "RAR_11_34") (pintype "passive"))
      (node (ref "U1") (pin "35") (pinfunction "VDD_CORE11_35") (pintype "passive"))
    )
    (net (code "70") (name "V_PWR_IN") (class "Default")
      (node (ref "C58") (pin "2") (pinfunction "2_2") (pintype "passive"))
      (node (ref "C59") (pin "2") (pinfunction "2_2") (pintype "passive"))
      (node (ref "L3") (pin "1") (pinfunction "1_1") (pintype "passive"))
      (node (ref "P1") (pin "1") (pinfunction "1_1") (pintype "passive"))
      (node (ref "Q3") (pin "1") (pinfunction "D_1") (pintype "passive"))
    )
    (net (code "71") (name "unconnected-(J1-RX1+-PadB11)") (class "Default")
      (node (ref "J1") (pin "B11") (pinfunction "RX1+_B11") (pintype "passive"))
    )
    (net (code "72") (name "unconnected-(J1-RX1--PadB10)") (class "Default")
      (node (ref "J1") (pin "B10") (pinfunction "RX1-_B10") (pintype "passive"))
    )
    (net (code "73") (name "unconnected-(J1-RX2+-PadA11)") (class "Default")
      (node (ref "J1") (pin "A11") (pinfunction "RX2+_A11") (pintype "passive"))
    )
    (net (code "74") (name "unconnected-(J1-RX2--PadA10)") (class "Default")
      (node (ref "J1") (pin "A10") (pinfunction "RX2-_A10") (pintype "passive"))
    )
    (net (code "75") (name "unconnected-(J1-SBU1-PadA8)") (class "Default")
      (node (ref "J1") (pin "A8") (pinfunction "SBU1_A8") (pintype "passive"))
    )
    (net (code "76") (name "unconnected-(J1-SBU2-PadB8)") (class "Default")
      (node (ref "J1") (pin "B8") (pinfunction "SBU2_B8") (pintype "passive"))
    )
    (net (code "77") (name "unconnected-(J1-TX1+-PadA2)") (class "Default")
      (node (ref "J1") (pin "A2") (pinfunction "TX1+_A2") (pintype "passive"))
    )
    (net (code "78") (name "unconnected-(J1-TX1--PadA3)") (class "Default")
      (node (ref "J1") (pin "A3") (pinfunction "TX1-_A3") (pintype "passive"))
    )
    (net (code "79") (name "unconnected-(J1-TX2+-PadB2)") (class "Default")
      (node (ref "J1") (pin "B2") (pinfunction "TX2+_B2") (pintype "passive"))
    )
    (net (code "80") (name "unconnected-(J1-TX2--PadB3)") (class "Default")
      (node (ref "J1") (pin "B3") (pinfunction "TX2-_B3") (pintype "passive"))
    )
    (net (code "81") (name "unconnected-(U1-ADC0_KEY-Pad46)") (class "Default")
      (node (ref "U1") (pin "46") (pinfunction "ADC0_KEY_46") (pintype "passive"))
    )
    (net (code "82") (name "unconnected-(U1-ADC1_KEY-Pad47)") (class "Default")
      (node (ref "U1") (pin "47") (pinfunction "ADC1_KEY_47") (pintype "passive"))
    )
    (net (code "83") (name "unconnected-(U1-ALWAYS_ON-Pad28)") (class "Default")
      (node (ref "U1") (pin "28") (pinfunction "ALWAYS_ON_28") (pintype "passive"))
    )
    (net (code "84") (name "unconnected-(U1-DMC_IN1-Pad14)") (class "Default")
      (node (ref "U1") (pin "14") (pinfunction "DMC_IN1_14") (pintype "passive"))
    )
    (net (code "85") (name "unconnected-(U1-DMIC_CLK11-Pad13)") (class "Default")
      (node (ref "U1") (pin "13") (pinfunction "DMIC_CLK11_13") (pintype "passive"))
    )
    (net (code "86") (name "unconnected-(U1-I2C1_CLK-Pad51)") (class "Default")
      (node (ref "U1") (pin "51") (pinfunction "I2C1_CLK_51") (pintype "passive"))
    )
    (net (code "87") (name "unconnected-(U1-I2C1_DAT-Pad50)") (class "Default")
      (node (ref "U1") (pin "50") (pinfunction "I2C1_DAT_50") (pintype "passive"))
    )
    (net (code "88") (name "unconnected-(U1-I2S1_CLK-Pad1)") (class "Default")
      (node (ref "U1") (pin "1") (pinfunction "I2S1_CLK_1") (pintype "passive"))
    )
    (net (code "89") (name "unconnected-(U1-I2S1_SDI-Pad3)") (class "Default")
      (node (ref "U1") (pin "3") (pinfunction "I2S1_SDI_3") (pintype "passive"))
    )
    (net (code "90") (name "unconnected-(U1-I2S1_SDO-Pad4)") (class "Default")
      (node (ref "U1") (pin "4") (pinfunction "I2S1_SDO_4") (pintype "passive"))
    )
    (net (code "91") (name "unconnected-(U1-I2S1_WS-Pad2)") (class "Default")
      (node (ref "U1") (pin "2") (pinfunction "I2S1_WS_2") (pintype "passive"))
    )
    (net (code "92") (name "unconnected-(U1-NC-Pad29)") (class "Default")
      (node (ref "U1") (pin "29") (pinfunction "NC_29") (pintype "passive"))
    )
    (net (code "93") (name "unconnected-(U1-P10{slash}I2C2_CLK-Pad32)") (class "Default")
      (node (ref "U1") (pin "32") (pinfunction "P10/I2C2_CLK_32") (pintype "passive"))
    )
    (net (code "94") (name "unconnected-(U1-P11{slash}I2C2_DAT-Pad33)") (class "Default")
      (node (ref "U1") (pin "33") (pinfunction "P11/I2C2_DAT_33") (pintype "passive"))
    )
    (net (code "95") (name "unconnected-(U1-VDD_IO33-Pad36)") (class "Default")
      (node (ref "U1") (pin "36") (pinfunction "VDD_IO33_36") (pintype "passive"))
    )
    (net (code "96") (name "unconnected-(U1-VDD_IP33-Pad37)") (class "Default")
      (node (ref "U1") (pin "37") (pinfunction "VDD_IP33_37") (pintype "passive"))
    )
  )
)
